# MicroPomodoro.net
KiCad netlist of a schematic drawn in EAGLE
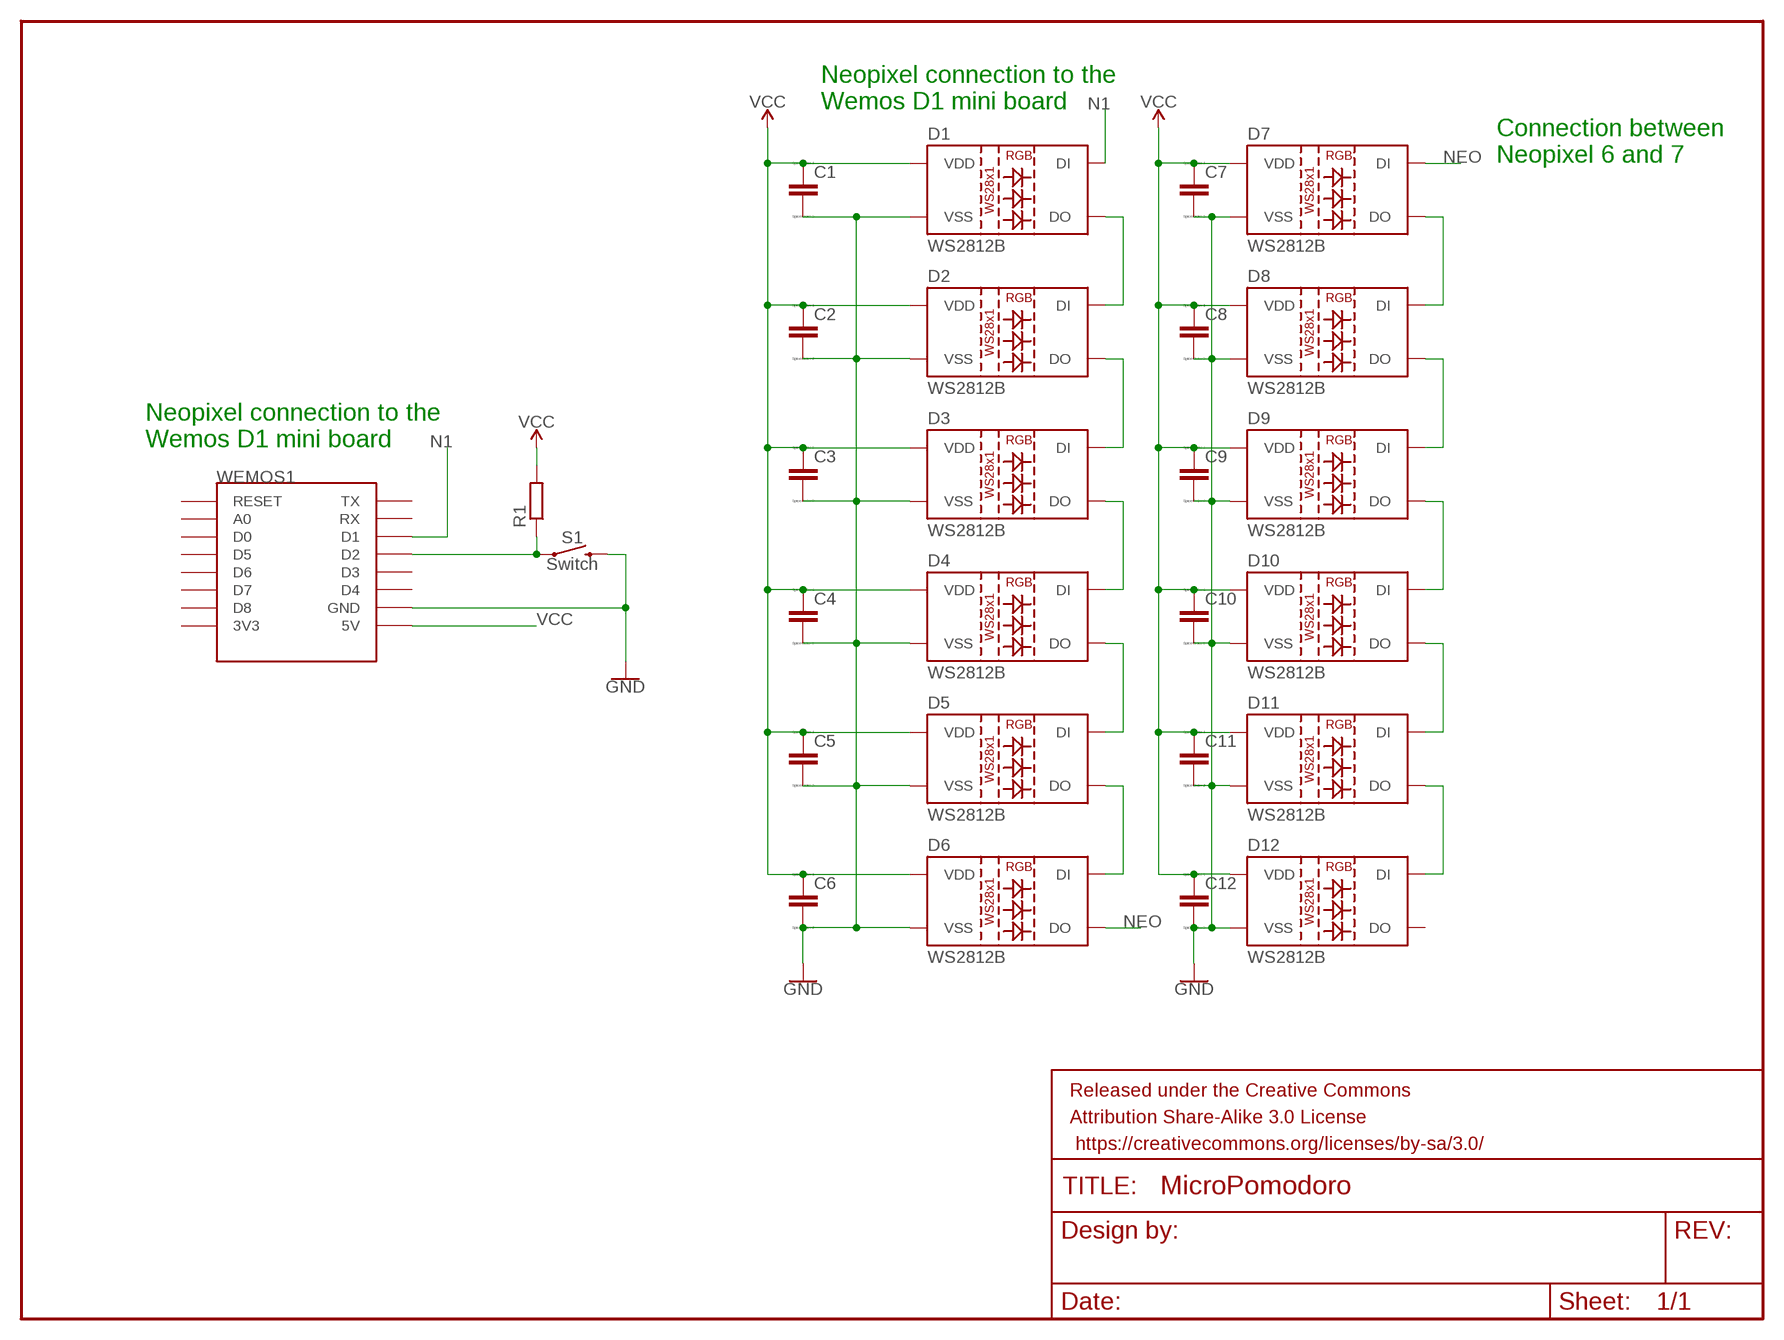
[diagram p0: schematic, sheet 1]

(export (version "E")
  (design (tool "Eeschema 10.0.6"))
  (components
    (comp (ref "C1")
      (value "CC1206")
      (footprint "eagle-import:C1206")
      (libsource (lib "eagle-import") (part "CC1206"))
    )
    (comp (ref "C2")
      (value "CC1206")
      (footprint "eagle-import:C1206")
      (libsource (lib "eagle-import") (part "CC1206"))
    )
    (comp (ref "C3")
      (value "CC1206")
      (footprint "eagle-import:C1206")
      (libsource (lib "eagle-import") (part "CC1206"))
    )
    (comp (ref "C4")
      (value "CC1206")
      (footprint "eagle-import:C1206")
      (libsource (lib "eagle-import") (part "CC1206"))
    )
    (comp (ref "C5")
      (value "CC1206")
      (footprint "eagle-import:C1206")
      (libsource (lib "eagle-import") (part "CC1206"))
    )
    (comp (ref "C6")
      (value "CC1206")
      (footprint "eagle-import:C1206")
      (libsource (lib "eagle-import") (part "CC1206"))
    )
    (comp (ref "C7")
      (value "CC1206")
      (footprint "eagle-import:C1206")
      (libsource (lib "eagle-import") (part "CC1206"))
    )
    (comp (ref "C8")
      (value "CC1206")
      (footprint "eagle-import:C1206")
      (libsource (lib "eagle-import") (part "CC1206"))
    )
    (comp (ref "C9")
      (value "CC1206")
      (footprint "eagle-import:C1206")
      (libsource (lib "eagle-import") (part "CC1206"))
    )
    (comp (ref "C10")
      (value "CC1206")
      (footprint "eagle-import:C1206")
      (libsource (lib "eagle-import") (part "CC1206"))
    )
    (comp (ref "C11")
      (value "CC1206")
      (footprint "eagle-import:C1206")
      (libsource (lib "eagle-import") (part "CC1206"))
    )
    (comp (ref "C12")
      (value "CC1206")
      (footprint "eagle-import:C1206")
      (libsource (lib "eagle-import") (part "CC1206"))
    )
    (comp (ref "D1")
      (value "WS2812B")
      (footprint "eagle-import:WS2812B")
      (libsource (lib "eagle-import") (part "WS2812B"))
    )
    (comp (ref "D2")
      (value "WS2812B")
      (footprint "eagle-import:WS2812B")
      (libsource (lib "eagle-import") (part "WS2812B"))
    )
    (comp (ref "D3")
      (value "WS2812B")
      (footprint "eagle-import:WS2812B")
      (libsource (lib "eagle-import") (part "WS2812B"))
    )
    (comp (ref "D4")
      (value "WS2812B")
      (footprint "eagle-import:WS2812B")
      (libsource (lib "eagle-import") (part "WS2812B"))
    )
    (comp (ref "D5")
      (value "WS2812B")
      (footprint "eagle-import:WS2812B")
      (libsource (lib "eagle-import") (part "WS2812B"))
    )
    (comp (ref "D6")
      (value "WS2812B")
      (footprint "eagle-import:WS2812B")
      (libsource (lib "eagle-import") (part "WS2812B"))
    )
    (comp (ref "D7")
      (value "WS2812B")
      (footprint "eagle-import:WS2812B")
      (libsource (lib "eagle-import") (part "WS2812B"))
    )
    (comp (ref "D8")
      (value "WS2812B")
      (footprint "eagle-import:WS2812B")
      (libsource (lib "eagle-import") (part "WS2812B"))
    )
    (comp (ref "D9")
      (value "WS2812B")
      (footprint "eagle-import:WS2812B")
      (libsource (lib "eagle-import") (part "WS2812B"))
    )
    (comp (ref "D10")
      (value "WS2812B")
      (footprint "eagle-import:WS2812B")
      (libsource (lib "eagle-import") (part "WS2812B"))
    )
    (comp (ref "D11")
      (value "WS2812B")
      (footprint "eagle-import:WS2812B")
      (libsource (lib "eagle-import") (part "WS2812B"))
    )
    (comp (ref "D12")
      (value "WS2812B")
      (footprint "eagle-import:WS2812B")
      (libsource (lib "eagle-import") (part "WS2812B"))
    )
    (comp (ref "FRAME1")
      (value "FRAME-LETTER")
      (footprint "eagle-import:CREATIVE_COMMONS")
      (libsource (lib "eagle-import") (part "FRAME-LETTER"))
    )
    (comp (ref "R1")
      (value "R-EU_R1206")
      (footprint "eagle-import:R1206")
      (libsource (lib "eagle-import") (part "R-EU_R1206"))
    )
    (comp (ref "S1")
      (value "Switch")
      (footprint "eagle-import:TACTILE_SWITCH_PTH_6.0MM")
      (libsource (lib "eagle-import") (part "MOMENTARY-SWITCH-SPST-PTH-6.0MM"))
    )
    (comp (ref "WEMOS1")
      (value "WEMOS-D1-MINI")
      (footprint "eagle-import:WEMOS-D1-MINI")
      (libsource (lib "eagle-import") (part "WEMOS-D1-MINI"))
    )
  )
  (nets
    (net (code "1") (name "/N1") (class "Default")
      (node (ref "D1") (pin "4") (pinfunction "DI_4") (pintype "bidirectional"))
      (node (ref "WEMOS1") (pin "D1") (pinfunction "D1_D1") (pintype "bidirectional"))
    )
    (net (code "2") (name "/NEO") (class "Default")
      (node (ref "D6") (pin "2") (pinfunction "DO_2") (pintype "bidirectional"))
      (node (ref "D7") (pin "4") (pinfunction "DI_4") (pintype "bidirectional"))
    )
    (net (code "3") (name "GND") (class "Default")
      (node (ref "C1") (pin "2") (pinfunction "2_2") (pintype "passive"))
      (node (ref "C10") (pin "2") (pinfunction "2_2") (pintype "passive"))
      (node (ref "C11") (pin "2") (pinfunction "2_2") (pintype "passive"))
      (node (ref "C12") (pin "2") (pinfunction "2_2") (pintype "passive"))
      (node (ref "C2") (pin "2") (pinfunction "2_2") (pintype "passive"))
      (node (ref "C3") (pin "2") (pinfunction "2_2") (pintype "passive"))
      (node (ref "C4") (pin "2") (pinfunction "2_2") (pintype "passive"))
      (node (ref "C5") (pin "2") (pinfunction "2_2") (pintype "passive"))
      (node (ref "C6") (pin "2") (pinfunction "2_2") (pintype "passive"))
      (node (ref "C7") (pin "2") (pinfunction "2_2") (pintype "passive"))
      (node (ref "C8") (pin "2") (pinfunction "2_2") (pintype "passive"))
      (node (ref "C9") (pin "2") (pinfunction "2_2") (pintype "passive"))
      (node (ref "D1") (pin "3") (pinfunction "VSS_3") (pintype "bidirectional"))
      (node (ref "D10") (pin "3") (pinfunction "VSS_3") (pintype "bidirectional"))
      (node (ref "D11") (pin "3") (pinfunction "VSS_3") (pintype "bidirectional"))
      (node (ref "D12") (pin "3") (pinfunction "VSS_3") (pintype "bidirectional"))
      (node (ref "D2") (pin "3") (pinfunction "VSS_3") (pintype "bidirectional"))
      (node (ref "D3") (pin "3") (pinfunction "VSS_3") (pintype "bidirectional"))
      (node (ref "D4") (pin "3") (pinfunction "VSS_3") (pintype "bidirectional"))
      (node (ref "D5") (pin "3") (pinfunction "VSS_3") (pintype "bidirectional"))
      (node (ref "D6") (pin "3") (pinfunction "VSS_3") (pintype "bidirectional"))
      (node (ref "D7") (pin "3") (pinfunction "VSS_3") (pintype "bidirectional"))
      (node (ref "D8") (pin "3") (pinfunction "VSS_3") (pintype "bidirectional"))
      (node (ref "D9") (pin "3") (pinfunction "VSS_3") (pintype "bidirectional"))
      (node (ref "S1") (pin "3") (pinfunction "2_3") (pintype "passive"))
      (node (ref "WEMOS1") (pin "GND") (pinfunction "GND_GND") (pintype "bidirectional"))
    )
    (net (code "4") (name "Net-(D1-DO)") (class "Default")
      (node (ref "D1") (pin "2") (pinfunction "DO_2") (pintype "bidirectional"))
      (node (ref "D2") (pin "4") (pinfunction "DI_4") (pintype "bidirectional"))
    )
    (net (code "5") (name "Net-(D2-DO)") (class "Default")
      (node (ref "D2") (pin "2") (pinfunction "DO_2") (pintype "bidirectional"))
      (node (ref "D3") (pin "4") (pinfunction "DI_4") (pintype "bidirectional"))
    )
    (net (code "6") (name "Net-(D3-DO)") (class "Default")
      (node (ref "D3") (pin "2") (pinfunction "DO_2") (pintype "bidirectional"))
      (node (ref "D4") (pin "4") (pinfunction "DI_4") (pintype "bidirectional"))
    )
    (net (code "7") (name "Net-(D4-DO)") (class "Default")
      (node (ref "D4") (pin "2") (pinfunction "DO_2") (pintype "bidirectional"))
      (node (ref "D5") (pin "4") (pinfunction "DI_4") (pintype "bidirectional"))
    )
    (net (code "8") (name "Net-(D5-DO)") (class "Default")
      (node (ref "D5") (pin "2") (pinfunction "DO_2") (pintype "bidirectional"))
      (node (ref "D6") (pin "4") (pinfunction "DI_4") (pintype "bidirectional"))
    )
    (net (code "9") (name "Net-(D7-DO)") (class "Default")
      (node (ref "D7") (pin "2") (pinfunction "DO_2") (pintype "bidirectional"))
      (node (ref "D8") (pin "4") (pinfunction "DI_4") (pintype "bidirectional"))
    )
    (net (code "10") (name "Net-(D8-DO)") (class "Default")
      (node (ref "D8") (pin "2") (pinfunction "DO_2") (pintype "bidirectional"))
      (node (ref "D9") (pin "4") (pinfunction "DI_4") (pintype "bidirectional"))
    )
    (net (code "11") (name "Net-(D10-DI)") (class "Default")
      (node (ref "D10") (pin "4") (pinfunction "DI_4") (pintype "bidirectional"))
      (node (ref "D9") (pin "2") (pinfunction "DO_2") (pintype "bidirectional"))
    )
    (net (code "12") (name "Net-(D10-DO)") (class "Default")
      (node (ref "D10") (pin "2") (pinfunction "DO_2") (pintype "bidirectional"))
      (node (ref "D11") (pin "4") (pinfunction "DI_4") (pintype "bidirectional"))
    )
    (net (code "13") (name "Net-(D11-DO)") (class "Default")
      (node (ref "D11") (pin "2") (pinfunction "DO_2") (pintype "bidirectional"))
      (node (ref "D12") (pin "4") (pinfunction "DI_4") (pintype "bidirectional"))
    )
    (net (code "14") (name "Net-(R1-Pad1)") (class "Default")
      (node (ref "R1") (pin "1") (pinfunction "1_1") (pintype "passive"))
      (node (ref "S1") (pin "1") (pinfunction "1_1") (pintype "passive"))
      (node (ref "WEMOS1") (pin "D2") (pinfunction "D2_D2") (pintype "bidirectional"))
    )
    (net (code "15") (name "VCC") (class "Default")
      (node (ref "C1") (pin "1") (pinfunction "1_1") (pintype "passive"))
      (node (ref "C10") (pin "1") (pinfunction "1_1") (pintype "passive"))
      (node (ref "C11") (pin "1") (pinfunction "1_1") (pintype "passive"))
      (node (ref "C12") (pin "1") (pinfunction "1_1") (pintype "passive"))
      (node (ref "C2") (pin "1") (pinfunction "1_1") (pintype "passive"))
      (node (ref "C3") (pin "1") (pinfunction "1_1") (pintype "passive"))
      (node (ref "C4") (pin "1") (pinfunction "1_1") (pintype "passive"))
      (node (ref "C5") (pin "1") (pinfunction "1_1") (pintype "passive"))
      (node (ref "C6") (pin "1") (pinfunction "1_1") (pintype "passive"))
      (node (ref "C7") (pin "1") (pinfunction "1_1") (pintype "passive"))
      (node (ref "C8") (pin "1") (pinfunction "1_1") (pintype "passive"))
      (node (ref "C9") (pin "1") (pinfunction "1_1") (pintype "passive"))
      (node (ref "D1") (pin "1") (pinfunction "VDD_1") (pintype "bidirectional"))
      (node (ref "D10") (pin "1") (pinfunction "VDD_1") (pintype "bidirectional"))
      (node (ref "D11") (pin "1") (pinfunction "VDD_1") (pintype "bidirectional"))
      (node (ref "D12") (pin "1") (pinfunction "VDD_1") (pintype "bidirectional"))
      (node (ref "D2") (pin "1") (pinfunction "VDD_1") (pintype "bidirectional"))
      (node (ref "D3") (pin "1") (pinfunction "VDD_1") (pintype "bidirectional"))
      (node (ref "D4") (pin "1") (pinfunction "VDD_1") (pintype "bidirectional"))
      (node (ref "D5") (pin "1") (pinfunction "VDD_1") (pintype "bidirectional"))
      (node (ref "D6") (pin "1") (pinfunction "VDD_1") (pintype "bidirectional"))
      (node (ref "D7") (pin "1") (pinfunction "VDD_1") (pintype "bidirectional"))
      (node (ref "D8") (pin "1") (pinfunction "VDD_1") (pintype "bidirectional"))
      (node (ref "D9") (pin "1") (pinfunction "VDD_1") (pintype "bidirectional"))
      (node (ref "R1") (pin "2") (pinfunction "2_2") (pintype "passive"))
      (node (ref "WEMOS1") (pin "5V") (pinfunction "5V_5V") (pintype "bidirectional"))
    )
    (net (code "16") (name "unconnected-(D12-DO-Pad2)") (class "Default")
      (node (ref "D12") (pin "2") (pinfunction "DO_2") (pintype "bidirectional"))
    )
    (net (code "17") (name "unconnected-(WEMOS1-Pad3V3)") (class "Default")
      (node (ref "WEMOS1") (pin "3V3") (pinfunction "3V3_3V3") (pintype "bidirectional"))
    )
    (net (code "18") (name "unconnected-(WEMOS1-PadA0)") (class "Default")
      (node (ref "WEMOS1") (pin "A0") (pinfunction "A0_A0") (pintype "bidirectional"))
    )
    (net (code "19") (name "unconnected-(WEMOS1-PadD0)") (class "Default")
      (node (ref "WEMOS1") (pin "D0") (pinfunction "D0_D0") (pintype "bidirectional"))
    )
    (net (code "20") (name "unconnected-(WEMOS1-PadD3)") (class "Default")
      (node (ref "WEMOS1") (pin "D3") (pinfunction "D3_D3") (pintype "bidirectional"))
    )
    (net (code "21") (name "unconnected-(WEMOS1-PadD4)") (class "Default")
      (node (ref "WEMOS1") (pin "D4") (pinfunction "D4_D4") (pintype "bidirectional"))
    )
    (net (code "22") (name "unconnected-(WEMOS1-PadD5)") (class "Default")
      (node (ref "WEMOS1") (pin "D5") (pinfunction "D5_D5") (pintype "bidirectional"))
    )
    (net (code "23") (name "unconnected-(WEMOS1-PadD6)") (class "Default")
      (node (ref "WEMOS1") (pin "D6") (pinfunction "D6_D6") (pintype "bidirectional"))
    )
    (net (code "24") (name "unconnected-(WEMOS1-PadD7)") (class "Default")
      (node (ref "WEMOS1") (pin "D7") (pinfunction "D7_D7") (pintype "bidirectional"))
    )
    (net (code "25") (name "unconnected-(WEMOS1-PadD8)") (class "Default")
      (node (ref "WEMOS1") (pin "D8") (pinfunction "D8_D8") (pintype "bidirectional"))
    )
    (net (code "26") (name "unconnected-(WEMOS1-PadRESET)") (class "Default")
      (node (ref "WEMOS1") (pin "RESET") (pinfunction "RESET_RESET") (pintype "bidirectional"))
    )
    (net (code "27") (name "unconnected-(WEMOS1-PadRX)") (class "Default")
      (node (ref "WEMOS1") (pin "RX") (pinfunction "RX_RX") (pintype "bidirectional"))
    )
    (net (code "28") (name "unconnected-(WEMOS1-PadTX)") (class "Default")
      (node (ref "WEMOS1") (pin "TX") (pinfunction "TX_TX") (pintype "bidirectional"))
    )
  )
)
